# Power_PMIC.net
KiCad netlist of a schematic drawn in Altium Designer
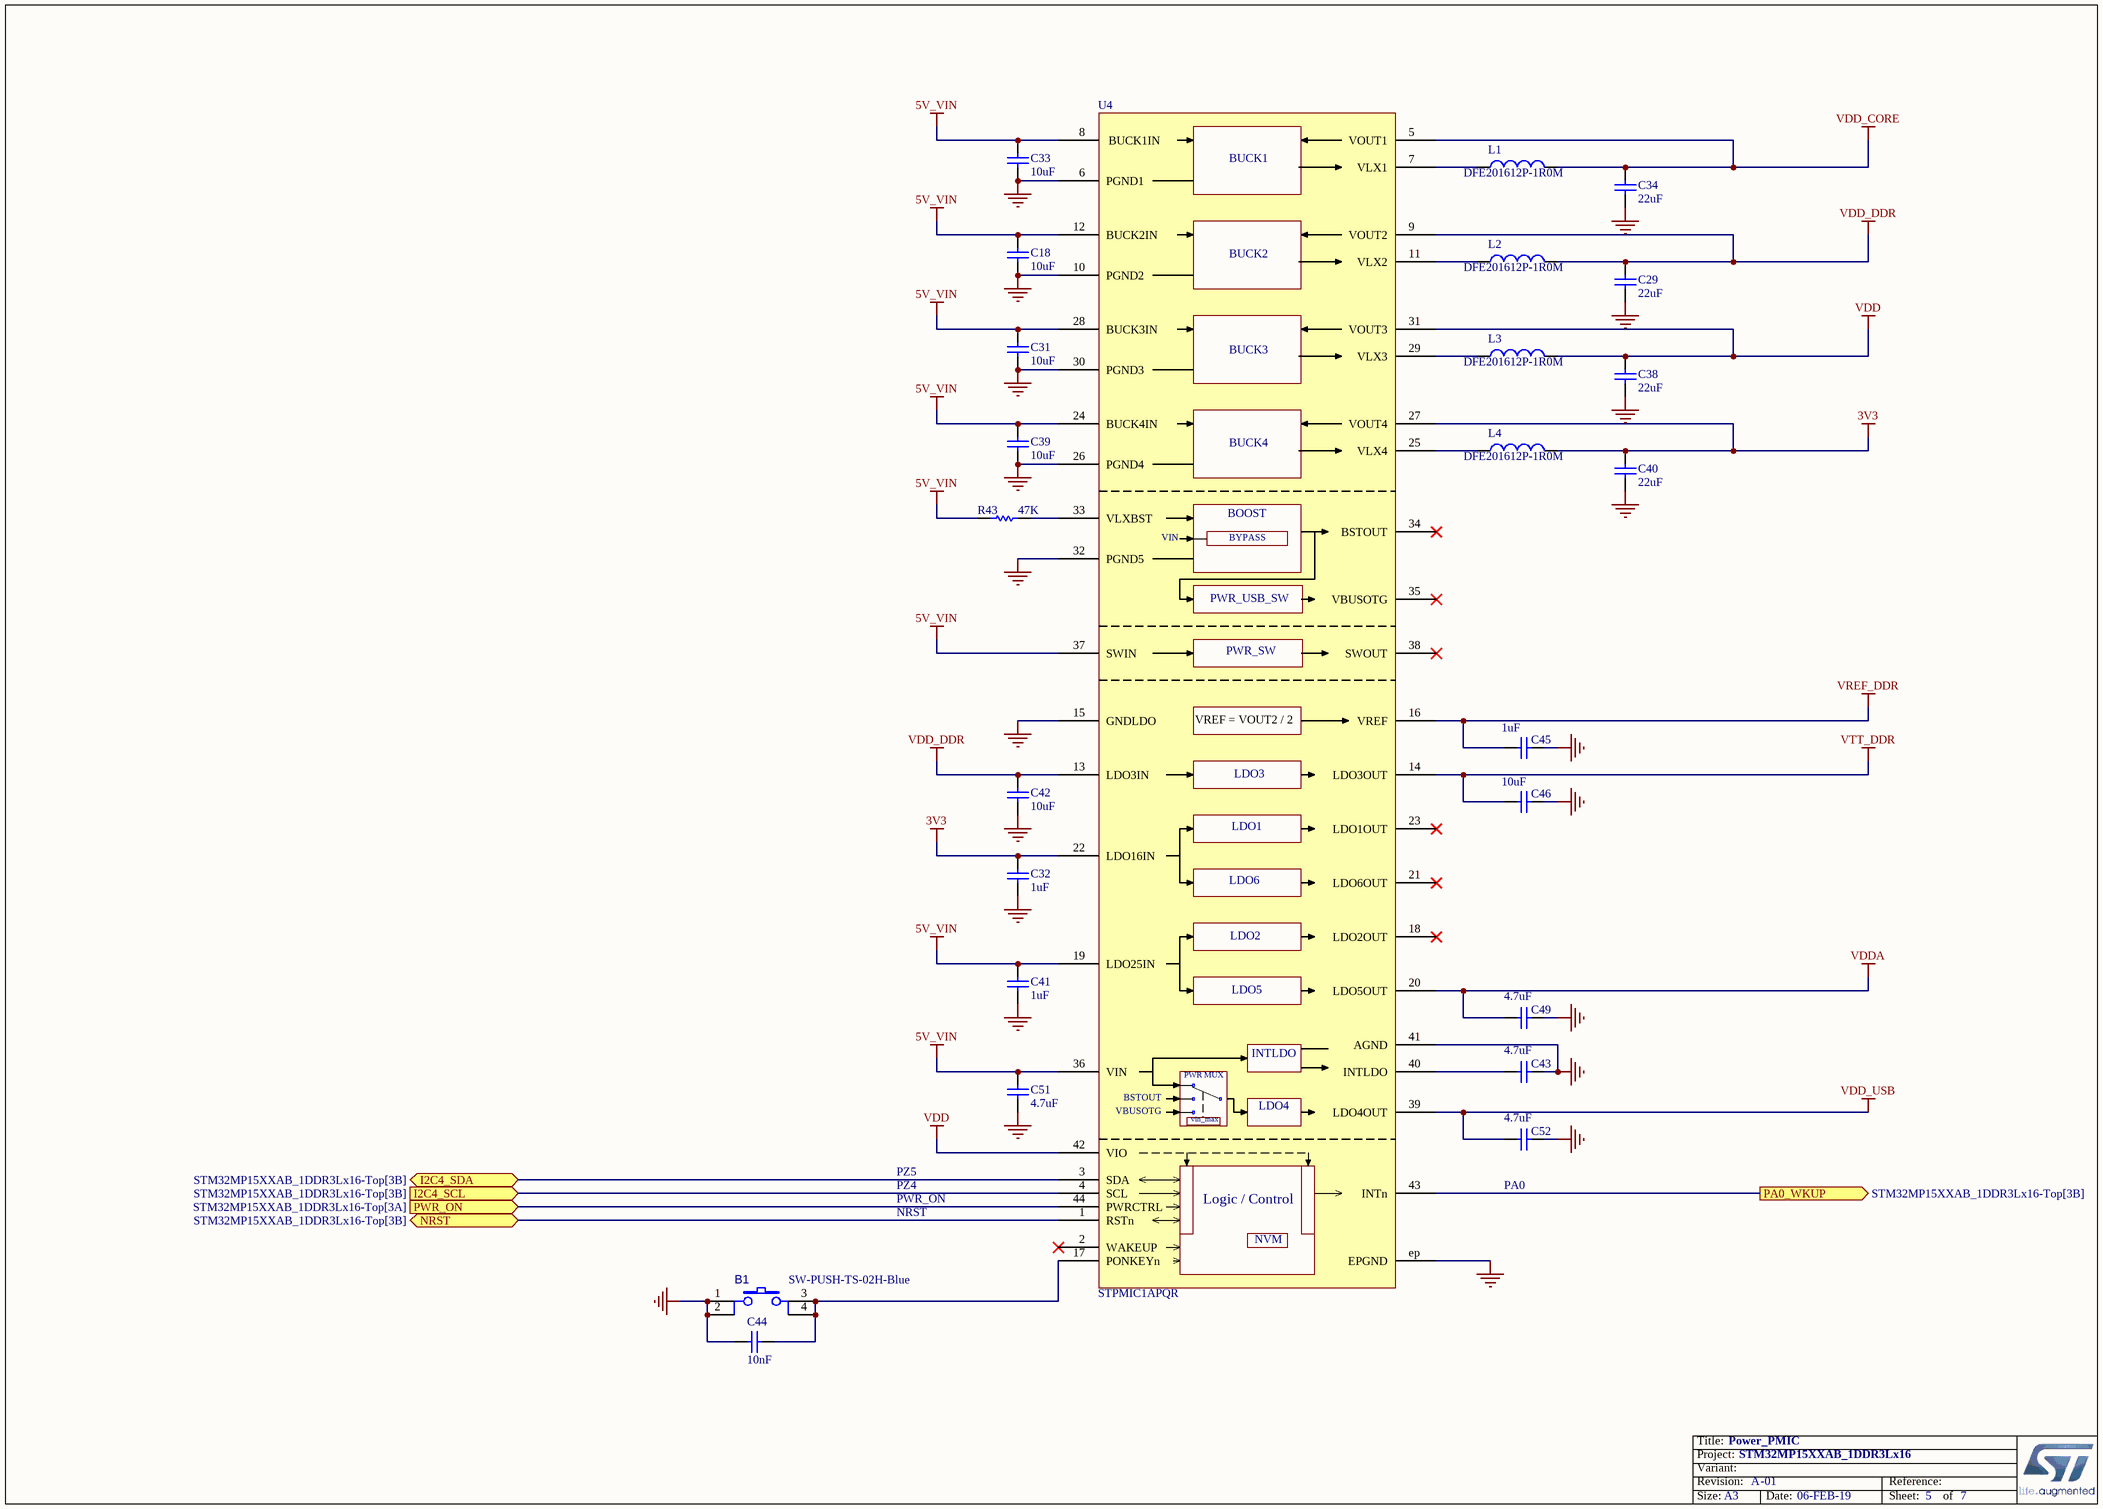
[diagram p0: Power_PMIC.SchDoc]

(export (version "E")
  (design (tool "Eeschema 10.0.6"))
  (components
    (comp (ref "B1")
      (value "SW-PUSH-TS-02H-Blue")
      (footprint "SWI_JIUBABA_C-TS-02H-2-5-B-V-T_R_BLUE")
      (description "Switch HW SMD blue")
      (fields
        (field (name "INTERNAL_PART_NUMBER") "MCD-00172")
        (field (name "MANUFACTURER_PART_NUMBER") "C-TS-02H-2.5-B-V-T/R BLUE")
        (field (name "PROVIDED_BY") "SUBCO")
      )
      (libsource (lib "MCD_PARTS_database") (part "SW-PUSH-TS-02H-Blue"))
    )
    (comp (ref "C18")
      (value "10uF")
      (footprint "C0603")
      (description "Capacitor, MLCC, 10uF, 10V, X5R, 10%, 0603, T=0,8mm")
      (fields
        (field (name "INTERNAL_PART_NUMBER") "MCD-00099")
        (field (name "MANUFACTURER_PART_NUMBER") "GRM188R61A106KE69D")
        (field (name "PROVIDED_BY") "SUBCO")
      )
      (libsource (lib "MCD_PARTS_database") (part "Capacitor"))
    )
    (comp (ref "C29")
      (value "22uF")
      (footprint "C0603")
      (description "Capacitor, MLCC, 22uF, 6V3, X5R, 20%, 0603, T=0,8mm")
      (fields
        (field (name "INTERNAL_PART_NUMBER") "MCD-00100")
        (field (name "MANUFACTURER_PART_NUMBER") "GRM188R60J226MEA0J")
        (field (name "PROVIDED_BY") "SUBCO")
      )
      (libsource (lib "MCD_PARTS_database") (part "Capacitor"))
    )
    (comp (ref "C31")
      (value "10uF")
      (footprint "C0603")
      (description "Capacitor, MLCC, 10uF, 10V, X5R, 10%, 0603, T=0,8mm")
      (fields
        (field (name "INTERNAL_PART_NUMBER") "MCD-00099")
        (field (name "MANUFACTURER_PART_NUMBER") "GRM188R61A106KE69D")
        (field (name "PROVIDED_BY") "SUBCO")
      )
      (libsource (lib "MCD_PARTS_database") (part "Capacitor"))
    )
    (comp (ref "C32")
      (value "1uF")
      (footprint "C0402")
      (description "Capacitor, MLCC, 1uF, 6V3, X5R, 10%, 0402, T=0,5mm")
      (fields
        (field (name "INTERNAL_PART_NUMBER") "MCD-00095")
        (field (name "MANUFACTURER_PART_NUMBER") "GRM155R61E105KA12")
        (field (name "PROVIDED_BY") "SUBCO")
      )
      (libsource (lib "MCD_PARTS_database") (part "Capacitor"))
    )
    (comp (ref "C33")
      (value "10uF")
      (footprint "C0603")
      (description "Capacitor, MLCC, 10uF, 10V, X5R, 10%, 0603, T=0,8mm")
      (fields
        (field (name "INTERNAL_PART_NUMBER") "MCD-00099")
        (field (name "MANUFACTURER_PART_NUMBER") "GRM188R61A106KE69D")
        (field (name "PROVIDED_BY") "SUBCO")
      )
      (libsource (lib "MCD_PARTS_database") (part "Capacitor"))
    )
    (comp (ref "C34")
      (value "22uF")
      (footprint "C0603")
      (description "Capacitor, MLCC, 22uF, 6V3, X5R, 20%, 0603, T=0,8mm")
      (fields
        (field (name "INTERNAL_PART_NUMBER") "MCD-00100")
        (field (name "MANUFACTURER_PART_NUMBER") "GRM188R60J226MEA0J")
        (field (name "PROVIDED_BY") "SUBCO")
      )
      (libsource (lib "MCD_PARTS_database") (part "Capacitor"))
    )
    (comp (ref "C38")
      (value "22uF")
      (footprint "C0603")
      (description "Capacitor, MLCC, 22uF, 6V3, X5R, 20%, 0603, T=0,8mm")
      (fields
        (field (name "INTERNAL_PART_NUMBER") "MCD-00100")
        (field (name "MANUFACTURER_PART_NUMBER") "GRM188R60J226MEA0J")
        (field (name "PROVIDED_BY") "SUBCO")
      )
      (libsource (lib "MCD_PARTS_database") (part "Capacitor"))
    )
    (comp (ref "C39")
      (value "10uF")
      (footprint "C0603")
      (description "Capacitor, MLCC, 10uF, 10V, X5R, 10%, 0603, T=0,8mm")
      (fields
        (field (name "INTERNAL_PART_NUMBER") "MCD-00099")
        (field (name "MANUFACTURER_PART_NUMBER") "GRM188R61A106KE69D")
        (field (name "PROVIDED_BY") "SUBCO")
      )
      (libsource (lib "MCD_PARTS_database") (part "Capacitor"))
    )
    (comp (ref "C40")
      (value "22uF")
      (footprint "C0603")
      (description "Capacitor, MLCC, 22uF, 6V3, X5R, 20%, 0603, T=0,8mm")
      (fields
        (field (name "INTERNAL_PART_NUMBER") "MCD-00100")
        (field (name "MANUFACTURER_PART_NUMBER") "GRM188R60J226MEA0J")
        (field (name "PROVIDED_BY") "SUBCO")
      )
      (libsource (lib "MCD_PARTS_database") (part "Capacitor"))
    )
    (comp (ref "C41")
      (value "1uF")
      (footprint "C0402")
      (description "Capacitor, MLCC, 1uF, 6V3, X5R, 10%, 0402, T=0,5mm")
      (fields
        (field (name "INTERNAL_PART_NUMBER") "MCD-00095")
        (field (name "MANUFACTURER_PART_NUMBER") "GRM155R61E105KA12")
        (field (name "PROVIDED_BY") "SUBCO")
      )
      (libsource (lib "MCD_PARTS_database") (part "Capacitor"))
    )
    (comp (ref "C42")
      (value "10uF")
      (footprint "C0603")
      (description "Capacitor, MLCC, 10uF, 10V, X5R, 10%, 0603, T=0,8mm")
      (fields
        (field (name "INTERNAL_PART_NUMBER") "MCD-00099")
        (field (name "MANUFACTURER_PART_NUMBER") "GRM188R61A106KE69D")
        (field (name "PROVIDED_BY") "SUBCO")
      )
      (libsource (lib "MCD_PARTS_database") (part "Capacitor"))
    )
    (comp (ref "C43")
      (value "4.7uF")
      (footprint "C0402")
      (description "Capacitor, MLCC, 4.7uF, 6V3, X5R, 20%, 0402, T=0,5mm")
      (fields
        (field (name "INTERNAL_PART_NUMBER") "MCD-01356")
        (field (name "MANUFACTURER_PART_NUMBER") "GRM155R60J475ME47")
        (field (name "PROVIDED_BY") "SUBCO")
      )
      (libsource (lib "MCD_PARTS_database") (part "Capacitor"))
    )
    (comp (ref "C44")
      (value "10nF")
      (footprint "C0402")
      (description "Capacitor, MLCC, 10nF, 16V, X7R, 10%, 0402, T=0.5mm")
      (fields
        (field (name "INTERNAL_PART_NUMBER") "MCD-00011")
        (field (name "MANUFACTURER_PART_NUMBER") "CC0402KRX7R7BB103")
        (field (name "PROVIDED_BY") "SUBCO")
      )
      (libsource (lib "MCD_PARTS_database") (part "Capacitor"))
    )
    (comp (ref "C45")
      (value "1uF")
      (footprint "C0402")
      (description "Capacitor, MLCC, 1uF, 6V3, X5R, 10%, 0402, T=0,5mm")
      (fields
        (field (name "INTERNAL_PART_NUMBER") "MCD-00095")
        (field (name "MANUFACTURER_PART_NUMBER") "GRM155R61E105KA12")
        (field (name "PROVIDED_BY") "SUBCO")
      )
      (libsource (lib "MCD_PARTS_database") (part "Capacitor"))
    )
    (comp (ref "C46")
      (value "10uF")
      (footprint "C0603")
      (description "Capacitor, MLCC, 10uF, 10V, X5R, 10%, 0603, T=0,8mm")
      (fields
        (field (name "INTERNAL_PART_NUMBER") "MCD-00099")
        (field (name "MANUFACTURER_PART_NUMBER") "GRM188R61A106KE69D")
        (field (name "PROVIDED_BY") "SUBCO")
      )
      (libsource (lib "MCD_PARTS_database") (part "Capacitor"))
    )
    (comp (ref "C49")
      (value "4.7uF")
      (footprint "C0402")
      (description "Capacitor, MLCC, 4.7uF, 6V3, X5R, 20%, 0402, T=0,5mm")
      (fields
        (field (name "INTERNAL_PART_NUMBER") "MCD-01356")
        (field (name "MANUFACTURER_PART_NUMBER") "GRM155R60J475ME47")
        (field (name "PROVIDED_BY") "SUBCO")
      )
      (libsource (lib "MCD_PARTS_database") (part "Capacitor"))
    )
    (comp (ref "C51")
      (value "4.7uF")
      (footprint "C0402")
      (description "Capacitor, MLCC, 4.7uF, 6V3, X5R, 20%, 0402, T=0,5mm")
      (fields
        (field (name "INTERNAL_PART_NUMBER") "MCD-01356")
        (field (name "MANUFACTURER_PART_NUMBER") "GRM155R60J475ME47")
        (field (name "PROVIDED_BY") "SUBCO")
      )
      (libsource (lib "MCD_PARTS_database") (part "Capacitor"))
    )
    (comp (ref "C52")
      (value "4.7uF")
      (footprint "C0402")
      (description "Capacitor, MLCC, 4.7uF, 6V3, X5R, 20%, 0402, T=0,5mm")
      (fields
        (field (name "INTERNAL_PART_NUMBER") "MCD-01356")
        (field (name "MANUFACTURER_PART_NUMBER") "GRM155R60J475ME47")
        (field (name "PROVIDED_BY") "SUBCO")
      )
      (libsource (lib "MCD_PARTS_database") (part "Capacitor"))
    )
    (comp (ref "L1")
      (value "DFE201612P-1R0M")
      (footprint "IND_MURATA_DFE201612P")
      (description "Inductors 1.0uH 54mOhms3.3A +/-20% 2016")
      (fields
        (field (name "INTERNAL_PART_NUMBER") "MCD-01491")
        (field (name "MANUFACTURER") "MURATA")
        (field (name "PROVIDED_BY") "SUBCO")
      )
      (libsource (lib "MCD_PARTS_database") (part "Inductor"))
    )
    (comp (ref "L2")
      (value "DFE201612P-1R0M")
      (footprint "IND_MURATA_DFE201612P")
      (description "Inductors 1.0uH 54mOhms3.3A +/-20% 2016")
      (fields
        (field (name "INTERNAL_PART_NUMBER") "MCD-01491")
        (field (name "MANUFACTURER") "MURATA")
        (field (name "PROVIDED_BY") "SUBCO")
      )
      (libsource (lib "MCD_PARTS_database") (part "Inductor"))
    )
    (comp (ref "L3")
      (value "DFE201612P-1R0M")
      (footprint "IND_MURATA_DFE201612P")
      (description "Inductors 1.0uH 54mOhms3.3A +/-20% 2016")
      (fields
        (field (name "INTERNAL_PART_NUMBER") "MCD-01491")
        (field (name "MANUFACTURER") "MURATA")
        (field (name "PROVIDED_BY") "SUBCO")
      )
      (libsource (lib "MCD_PARTS_database") (part "Inductor"))
    )
    (comp (ref "L4")
      (value "DFE201612P-1R0M")
      (footprint "IND_MURATA_DFE201612P")
      (description "Inductors 1.0uH 54mOhms3.3A +/-20% 2016")
      (fields
        (field (name "INTERNAL_PART_NUMBER") "MCD-01491")
        (field (name "MANUFACTURER") "MURATA")
        (field (name "PROVIDED_BY") "SUBCO")
      )
      (libsource (lib "MCD_PARTS_database") (part "Inductor"))
    )
    (comp (ref "R43")
      (value "47K")
      (footprint "R0402")
      (description "Resistor,47K,0402,1%,1/16W")
      (fields
        (field (name "INTERNAL_PART_NUMBER") "MCD-00063")
        (field (name "MANUFACTURER_PART_NUMBER") "RC0402FR-0747KL")
        (field (name "PROVIDED_BY") "SUBCO")
      )
      (libsource (lib "MCD_PARTS_database") (part "Resistor"))
    )
    (comp (ref "U4")
      (value "STPMIC1APQR")
      (footprint "ICC_WFQFN44-EPAD_5X6_P040")
      (fields
        (field (name "INTERNAL_PART_NUMBER") "MCD-01650")
        (field (name "MANUFACTURER") "STMICROELECTRONICS")
        (field (name "PROVIDED_BY") "SUBCO with ST control")
      )
      (libsource (lib "MCD_PARTS_database") (part "STPMU1"))
    )
  )
  (nets
    (net (code "1") (name "/I2C4_SCL") (class "Default")
      (node (ref "U4") (pin "4") (pinfunction "SCL_4") (pintype "passive"))
    )
    (net (code "2") (name "/I2C4_SDA") (class "Default")
      (node (ref "U4") (pin "3") (pinfunction "SDA_3") (pintype "passive"))
    )
    (net (code "3") (name "/NRST") (class "Default")
      (node (ref "U4") (pin "1") (pinfunction "RSTn_1") (pintype "passive"))
    )
    (net (code "4") (name "/PA0_WKUP") (class "Default")
      (node (ref "U4") (pin "43") (pinfunction "INTn_43") (pintype "passive"))
    )
    (net (code "5") (name "/PWR_ON") (class "Default")
      (node (ref "U4") (pin "44") (pinfunction "PWRCTRL_44") (pintype "passive"))
    )
    (net (code "6") (name "3V3") (class "Default")
      (node (ref "C32") (pin "2") (pinfunction "2_2") (pintype "passive"))
      (node (ref "C40") (pin "2") (pinfunction "2_2") (pintype "passive"))
      (node (ref "L4") (pin "2") (pinfunction "2_2") (pintype "passive"))
      (node (ref "U4") (pin "22") (pinfunction "LDO16IN_22") (pintype "passive"))
      (node (ref "U4") (pin "27") (pinfunction "VOUT4_27") (pintype "passive"))
    )
    (net (code "7") (name "5V_VIN") (class "Default")
      (node (ref "C18") (pin "2") (pinfunction "2_2") (pintype "passive"))
      (node (ref "C31") (pin "2") (pinfunction "2_2") (pintype "passive"))
      (node (ref "C33") (pin "2") (pinfunction "2_2") (pintype "passive"))
      (node (ref "C39") (pin "2") (pinfunction "2_2") (pintype "passive"))
      (node (ref "C41") (pin "2") (pinfunction "2_2") (pintype "passive"))
      (node (ref "C51") (pin "1") (pinfunction "1_1") (pintype "passive"))
      (node (ref "R43") (pin "2") (pinfunction "2_2") (pintype "passive"))
      (node (ref "U4") (pin "12") (pinfunction "BUCK2IN_12") (pintype "passive"))
      (node (ref "U4") (pin "19") (pinfunction "LDO25IN_19") (pintype "passive"))
      (node (ref "U4") (pin "24") (pinfunction "BUCK4IN_24") (pintype "passive"))
      (node (ref "U4") (pin "28") (pinfunction "BUCK3IN_28") (pintype "passive"))
      (node (ref "U4") (pin "36") (pinfunction "VIN_36") (pintype "passive"))
      (node (ref "U4") (pin "37") (pinfunction "SWIN_37") (pintype "passive"))
      (node (ref "U4") (pin "8") (pinfunction "BUCK1IN_8") (pintype "passive"))
    )
    (net (code "8") (name "GND") (class "Default")
      (node (ref "B1") (pin "1") (pinfunction "1_1") (pintype "passive"))
      (node (ref "B1") (pin "2") (pinfunction "2_2") (pintype "passive"))
      (node (ref "C18") (pin "1") (pinfunction "1_1") (pintype "passive"))
      (node (ref "C29") (pin "1") (pinfunction "1_1") (pintype "passive"))
      (node (ref "C31") (pin "1") (pinfunction "1_1") (pintype "passive"))
      (node (ref "C32") (pin "1") (pinfunction "1_1") (pintype "passive"))
      (node (ref "C33") (pin "1") (pinfunction "1_1") (pintype "passive"))
      (node (ref "C34") (pin "1") (pinfunction "1_1") (pintype "passive"))
      (node (ref "C38") (pin "1") (pinfunction "1_1") (pintype "passive"))
      (node (ref "C39") (pin "1") (pinfunction "1_1") (pintype "passive"))
      (node (ref "C40") (pin "1") (pinfunction "1_1") (pintype "passive"))
      (node (ref "C41") (pin "1") (pinfunction "1_1") (pintype "passive"))
      (node (ref "C42") (pin "1") (pinfunction "1_1") (pintype "passive"))
      (node (ref "C43") (pin "1") (pinfunction "1_1") (pintype "passive"))
      (node (ref "C44") (pin "1") (pinfunction "1_1") (pintype "passive"))
      (node (ref "C45") (pin "1") (pinfunction "1_1") (pintype "passive"))
      (node (ref "C46") (pin "1") (pinfunction "1_1") (pintype "passive"))
      (node (ref "C49") (pin "1") (pinfunction "1_1") (pintype "passive"))
      (node (ref "C51") (pin "2") (pinfunction "2_2") (pintype "passive"))
      (node (ref "C52") (pin "1") (pinfunction "1_1") (pintype "passive"))
      (node (ref "U4") (pin "10") (pinfunction "PGND2_10") (pintype "passive"))
      (node (ref "U4") (pin "15") (pinfunction "GNDLDO_15") (pintype "passive"))
      (node (ref "U4") (pin "26") (pinfunction "PGND4_26") (pintype "passive"))
      (node (ref "U4") (pin "30") (pinfunction "PGND3_30") (pintype "passive"))
      (node (ref "U4") (pin "32") (pinfunction "PGND5_32") (pintype "passive"))
      (node (ref "U4") (pin "41") (pinfunction "AGND_41") (pintype "passive"))
      (node (ref "U4") (pin "6") (pinfunction "PGND1_6") (pintype "passive"))
      (node (ref "U4") (pin "ep") (pinfunction "EPGND_ep") (pintype "passive"))
    )
    (net (code "9") (name "Net-(U4-INTLDO)") (class "Default")
      (node (ref "C43") (pin "2") (pinfunction "2_2") (pintype "passive"))
      (node (ref "U4") (pin "40") (pinfunction "INTLDO_40") (pintype "passive"))
    )
    (net (code "10") (name "Net-(U4-PONKEYn)") (class "Default")
      (node (ref "B1") (pin "3") (pinfunction "3_3") (pintype "passive"))
      (node (ref "B1") (pin "4") (pinfunction "4_4") (pintype "passive"))
      (node (ref "C44") (pin "2") (pinfunction "2_2") (pintype "passive"))
      (node (ref "U4") (pin "17") (pinfunction "PONKEYn_17") (pintype "passive"))
    )
    (net (code "11") (name "Net-(U4-VLX1)") (class "Default")
      (node (ref "L1") (pin "1") (pinfunction "1_1") (pintype "passive"))
      (node (ref "U4") (pin "7") (pinfunction "VLX1_7") (pintype "passive"))
    )
    (net (code "12") (name "Net-(U4-VLX2)") (class "Default")
      (node (ref "L2") (pin "1") (pinfunction "1_1") (pintype "passive"))
      (node (ref "U4") (pin "11") (pinfunction "VLX2_11") (pintype "passive"))
    )
    (net (code "13") (name "Net-(U4-VLX3)") (class "Default")
      (node (ref "L3") (pin "1") (pinfunction "1_1") (pintype "passive"))
      (node (ref "U4") (pin "29") (pinfunction "VLX3_29") (pintype "passive"))
    )
    (net (code "14") (name "Net-(U4-VLX4)") (class "Default")
      (node (ref "L4") (pin "1") (pinfunction "1_1") (pintype "passive"))
      (node (ref "U4") (pin "25") (pinfunction "VLX4_25") (pintype "passive"))
    )
    (net (code "15") (name "Net-(U4-VLXBST)") (class "Default")
      (node (ref "R43") (pin "1") (pinfunction "1_1") (pintype "passive"))
      (node (ref "U4") (pin "33") (pinfunction "VLXBST_33") (pintype "passive"))
    )
    (net (code "16") (name "VDD") (class "Default")
      (node (ref "C38") (pin "2") (pinfunction "2_2") (pintype "passive"))
      (node (ref "L3") (pin "2") (pinfunction "2_2") (pintype "passive"))
      (node (ref "U4") (pin "31") (pinfunction "VOUT3_31") (pintype "passive"))
      (node (ref "U4") (pin "42") (pinfunction "VIO_42") (pintype "passive"))
    )
    (net (code "17") (name "VDDA") (class "Default")
      (node (ref "C49") (pin "2") (pinfunction "2_2") (pintype "passive"))
      (node (ref "U4") (pin "20") (pinfunction "LDO5OUT_20") (pintype "passive"))
    )
    (net (code "18") (name "VDD_CORE") (class "Default")
      (node (ref "C34") (pin "2") (pinfunction "2_2") (pintype "passive"))
      (node (ref "L1") (pin "2") (pinfunction "2_2") (pintype "passive"))
      (node (ref "U4") (pin "5") (pinfunction "VOUT1_5") (pintype "passive"))
    )
    (net (code "19") (name "VDD_DDR") (class "Default")
      (node (ref "C29") (pin "2") (pinfunction "2_2") (pintype "passive"))
      (node (ref "C42") (pin "2") (pinfunction "2_2") (pintype "passive"))
      (node (ref "L2") (pin "2") (pinfunction "2_2") (pintype "passive"))
      (node (ref "U4") (pin "13") (pinfunction "LDO3IN_13") (pintype "passive"))
      (node (ref "U4") (pin "9") (pinfunction "VOUT2_9") (pintype "passive"))
    )
    (net (code "20") (name "VDD_USB") (class "Default")
      (node (ref "C52") (pin "2") (pinfunction "2_2") (pintype "passive"))
      (node (ref "U4") (pin "39") (pinfunction "LDO4OUT_39") (pintype "passive"))
    )
    (net (code "21") (name "VREF_DDR") (class "Default")
      (node (ref "C45") (pin "2") (pinfunction "2_2") (pintype "passive"))
      (node (ref "U4") (pin "16") (pinfunction "VREF_16") (pintype "passive"))
    )
    (net (code "22") (name "VTT_DDR") (class "Default")
      (node (ref "C46") (pin "2") (pinfunction "2_2") (pintype "passive"))
      (node (ref "U4") (pin "14") (pinfunction "LDO3OUT_14") (pintype "passive"))
    )
    (net (code "23") (name "unconnected-(U4-BSTOUT-Pad34)") (class "Default")
      (node (ref "U4") (pin "34") (pinfunction "BSTOUT_34") (pintype "passive+no_connect"))
    )
    (net (code "24") (name "unconnected-(U4-LDO1OUT-Pad23)") (class "Default")
      (node (ref "U4") (pin "23") (pinfunction "LDO1OUT_23") (pintype "passive+no_connect"))
    )
    (net (code "25") (name "unconnected-(U4-LDO2OUT-Pad18)") (class "Default")
      (node (ref "U4") (pin "18") (pinfunction "LDO2OUT_18") (pintype "passive+no_connect"))
    )
    (net (code "26") (name "unconnected-(U4-LDO6OUT-Pad21)") (class "Default")
      (node (ref "U4") (pin "21") (pinfunction "LDO6OUT_21") (pintype "passive+no_connect"))
    )
    (net (code "27") (name "unconnected-(U4-SWOUT-Pad38)") (class "Default")
      (node (ref "U4") (pin "38") (pinfunction "SWOUT_38") (pintype "passive+no_connect"))
    )
    (net (code "28") (name "unconnected-(U4-VBUSOTG-Pad35)") (class "Default")
      (node (ref "U4") (pin "35") (pinfunction "VBUSOTG_35") (pintype "passive+no_connect"))
    )
    (net (code "29") (name "unconnected-(U4-WAKEUP-Pad2)") (class "Default")
      (node (ref "U4") (pin "2") (pinfunction "WAKEUP_2") (pintype "passive+no_connect"))
    )
  )
)
